# vswr_power_eagle.net
KiCad netlist of a schematic drawn in EAGLE
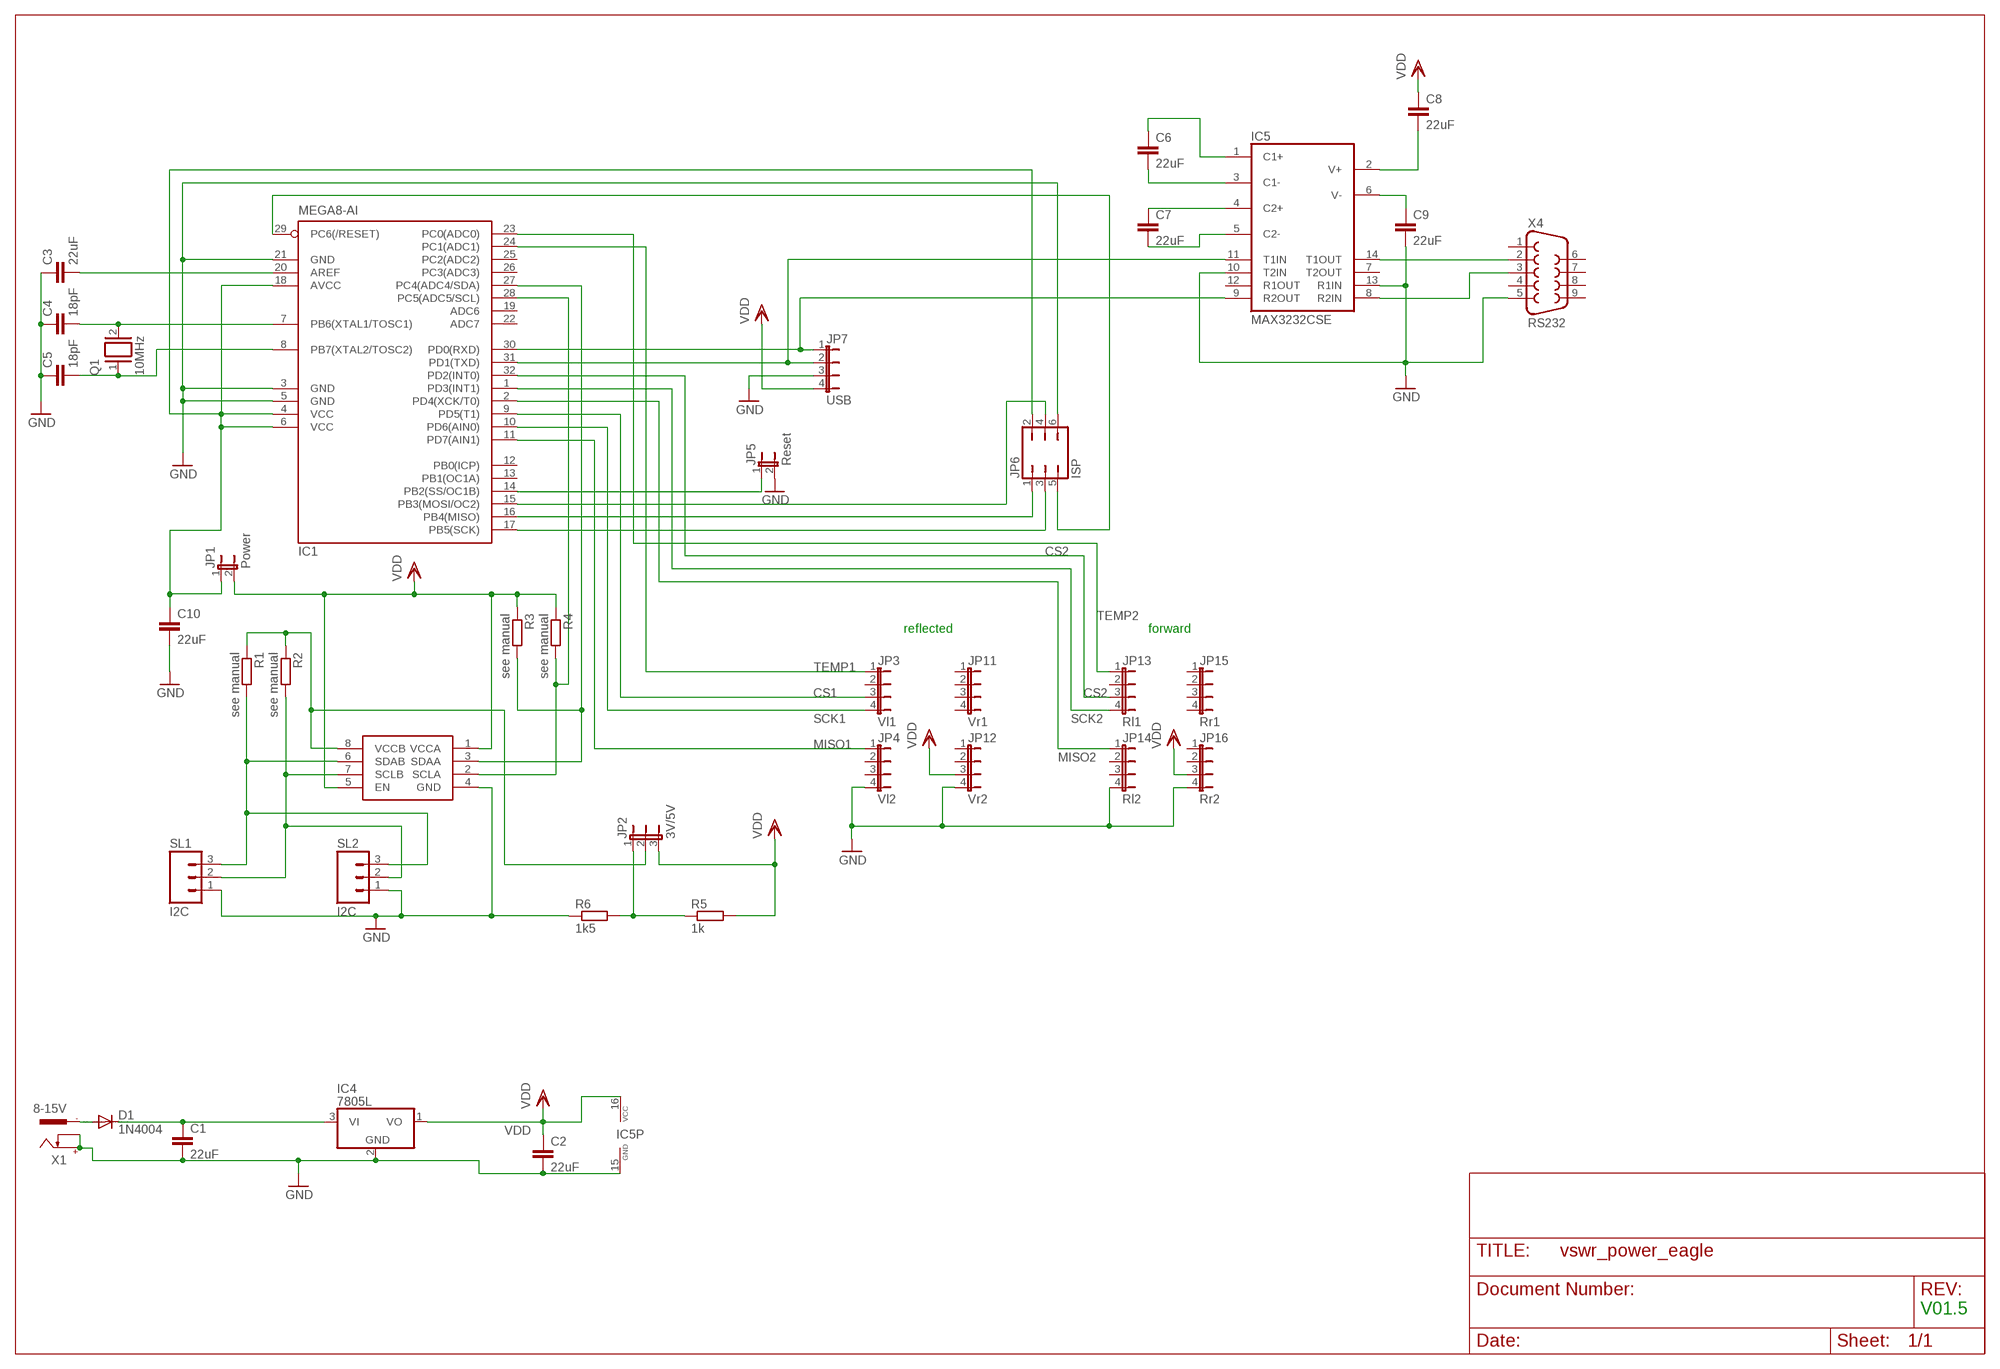
[diagram p0: schematic, sheet 1]

(export (version "E")
  (design (tool "Eeschema 10.0.6"))
  (components
    (comp (ref "C1")
      (value "22uF")
      (footprint "eagle-import:C1206")
      (libsource (lib "eagle-import") (part "C-EUC1206"))
    )
    (comp (ref "C2")
      (value "22uF")
      (footprint "eagle-import:C1206")
      (libsource (lib "eagle-import") (part "C-EUC1206"))
    )
    (comp (ref "C3")
      (value "22uF")
      (footprint "eagle-import:C1206")
      (libsource (lib "eagle-import") (part "C-EUC1206"))
    )
    (comp (ref "C4")
      (value "18pF")
      (footprint "eagle-import:C025-025X050")
      (libsource (lib "eagle-import") (part "resistor_C-EU025-025X050"))
    )
    (comp (ref "C5")
      (value "18pF")
      (footprint "eagle-import:C025-025X050")
      (libsource (lib "eagle-import") (part "resistor_C-EU025-025X050"))
    )
    (comp (ref "C6")
      (value "22uF")
      (footprint "eagle-import:C1206")
      (libsource (lib "eagle-import") (part "C-EUC1206"))
    )
    (comp (ref "C7")
      (value "22uF")
      (footprint "eagle-import:C1206")
      (libsource (lib "eagle-import") (part "C-EUC1206"))
    )
    (comp (ref "C8")
      (value "22uF")
      (footprint "eagle-import:C1206")
      (libsource (lib "eagle-import") (part "C-EUC1206"))
    )
    (comp (ref "C9")
      (value "22uF")
      (footprint "eagle-import:C1206")
      (libsource (lib "eagle-import") (part "C-EUC1206"))
    )
    (comp (ref "C10")
      (value "22uF")
      (footprint "eagle-import:C1206")
      (libsource (lib "eagle-import") (part "C-EUC1206"))
    )
    (comp (ref "D1")
      (value "1N4004")
      (footprint "eagle-import:DO41-10")
      (libsource (lib "eagle-import") (part "1N4004"))
    )
    (comp (ref "IC1")
      (value "MEGA8-AI")
      (footprint "eagle-import:TQFP32-08")
      (fields (field (name "MPN") "ATMEGA8-16AU"))
      (libsource (lib "eagle-import") (part "MEGA8-AI"))
    )
    (comp (ref "IC3")
      (value "PCA9517")
      (footprint "eagle-import:SO-08")
      (libsource (lib "eagle-import") (part "PCA9517"))
    )
    (comp (ref "IC4")
      (value "7805L")
      (footprint "eagle-import:TO92")
      (libsource (lib "eagle-import") (part "78L05"))
    )
    (comp (ref "IC5")
      (value "MAX3232CSE")
      (footprint "eagle-import:SO16")
      (libsource (lib "eagle-import") (part "MAX3232SEC"))
    )
    (comp (ref "JP1")
      (value "Power")
      (footprint "eagle-import:JP1")
      (libsource (lib "eagle-import") (part "JP1E"))
    )
    (comp (ref "JP2")
      (value "3V/5V")
      (footprint "eagle-import:JP2")
      (libsource (lib "eagle-import") (part "JP2E"))
    )
    (comp (ref "JP3")
      (value "Vl1")
      (footprint "eagle-import:JP4")
      (libsource (lib "eagle-import") (part "JP4E"))
    )
    (comp (ref "JP4")
      (value "Vl2")
      (footprint "eagle-import:JP4")
      (libsource (lib "eagle-import") (part "JP4E"))
    )
    (comp (ref "JP5")
      (value "Reset")
      (footprint "eagle-import:JP1")
      (libsource (lib "eagle-import") (part "JP1E"))
    )
    (comp (ref "JP6")
      (value "ISP")
      (footprint "eagle-import:JP3Q")
      (libsource (lib "eagle-import") (part "JP3Q"))
    )
    (comp (ref "JP7")
      (value "USB")
      (footprint "eagle-import:JP4")
      (libsource (lib "eagle-import") (part "JP4E"))
    )
    (comp (ref "JP11")
      (value "Vr1")
      (footprint "eagle-import:JP4")
      (libsource (lib "eagle-import") (part "JP4E"))
    )
    (comp (ref "JP12")
      (value "Vr2")
      (footprint "eagle-import:JP4")
      (libsource (lib "eagle-import") (part "JP4E"))
    )
    (comp (ref "JP13")
      (value "Rl1")
      (footprint "eagle-import:JP4")
      (libsource (lib "eagle-import") (part "JP4E"))
    )
    (comp (ref "JP14")
      (value "Rl2")
      (footprint "eagle-import:JP4")
      (libsource (lib "eagle-import") (part "JP4E"))
    )
    (comp (ref "JP15")
      (value "Rr1")
      (footprint "eagle-import:JP4")
      (libsource (lib "eagle-import") (part "JP4E"))
    )
    (comp (ref "JP16")
      (value "Rr2")
      (footprint "eagle-import:JP4")
      (libsource (lib "eagle-import") (part "JP4E"))
    )
    (comp (ref "Q1")
      (value "10MHz")
      (footprint "eagle-import:QS")
      (libsource (lib "eagle-import") (part "XTAL/S"))
    )
    (comp (ref "R1")
      (value "see manual")
      (footprint "eagle-import:R1206")
      (libsource (lib "eagle-import") (part "R-EU_R1206"))
    )
    (comp (ref "R2")
      (value "see manual")
      (footprint "eagle-import:R1206")
      (libsource (lib "eagle-import") (part "R-EU_R1206"))
    )
    (comp (ref "R3")
      (value "see manual")
      (footprint "eagle-import:R1206")
      (libsource (lib "eagle-import") (part "R-EU_R1206"))
    )
    (comp (ref "R4")
      (value "see manual")
      (footprint "eagle-import:R1206")
      (libsource (lib "eagle-import") (part "R-EU_R1206"))
    )
    (comp (ref "R5")
      (value "1k")
      (footprint "eagle-import:R1206")
      (libsource (lib "eagle-import") (part "R-EU_R1206"))
    )
    (comp (ref "R6")
      (value "1k5")
      (footprint "eagle-import:R1206")
      (libsource (lib "eagle-import") (part "R-EU_R1206"))
    )
    (comp (ref "SL1")
      (value "I2C")
      (footprint "eagle-import:03P")
      (libsource (lib "eagle-import") (part "M03"))
    )
    (comp (ref "SL2")
      (value "I2C")
      (footprint "eagle-import:03P")
      (libsource (lib "eagle-import") (part "M03"))
    )
    (comp (ref "X1")
      (value "8-15V")
      (footprint "eagle-import:737992-5")
      (libsource (lib "eagle-import") (part "737992-55"))
    )
    (comp (ref "X4")
      (value "RS232")
      (footprint "eagle-import:F09H")
      (libsource (lib "eagle-import") (part "F09H"))
    )
  )
  (nets
    (net (code "1") (name "/CS1") (class "Default")
      (node (ref "IC1") (pin "9") (pinfunction "PD5(T1)_9") (pintype "bidirectional"))
      (node (ref "JP3") (pin "3") (pinfunction "3_3") (pintype "passive"))
    )
    (net (code "2") (name "/CS2") (class "Default")
      (node (ref "IC1") (pin "32") (pinfunction "PD2(INT0)_32") (pintype "bidirectional"))
      (node (ref "JP13") (pin "3") (pinfunction "3_3") (pintype "passive"))
    )
    (net (code "3") (name "/MISO1") (class "Default")
      (node (ref "IC1") (pin "11") (pinfunction "PD7(AIN1)_11") (pintype "bidirectional"))
      (node (ref "JP4") (pin "1") (pinfunction "1_1") (pintype "passive"))
    )
    (net (code "4") (name "/MISO2") (class "Default")
      (node (ref "IC1") (pin "2") (pinfunction "PD4(XCK/T0)_2") (pintype "bidirectional"))
      (node (ref "JP14") (pin "1") (pinfunction "1_1") (pintype "passive"))
    )
    (net (code "5") (name "/SCK1") (class "Default")
      (node (ref "IC1") (pin "10") (pinfunction "PD6(AIN0)_10") (pintype "bidirectional"))
      (node (ref "JP3") (pin "4") (pinfunction "4_4") (pintype "passive"))
    )
    (net (code "6") (name "/SCK2") (class "Default")
      (node (ref "IC1") (pin "1") (pinfunction "PD3(INT1)_1") (pintype "bidirectional"))
      (node (ref "JP13") (pin "4") (pinfunction "4_4") (pintype "passive"))
    )
    (net (code "7") (name "/TEMP1") (class "Default")
      (node (ref "IC1") (pin "24") (pinfunction "PC1(ADC1)_24") (pintype "bidirectional"))
      (node (ref "JP3") (pin "1") (pinfunction "1_1") (pintype "passive"))
    )
    (net (code "8") (name "/TEMP2") (class "Default")
      (node (ref "IC1") (pin "23") (pinfunction "PC0(ADC0)_23") (pintype "bidirectional"))
      (node (ref "JP13") (pin "1") (pinfunction "1_1") (pintype "passive"))
    )
    (net (code "9") (name "GND") (class "Default")
      (node (ref "C1") (pin "2") (pinfunction "2_2") (pintype "passive"))
      (node (ref "C10") (pin "2") (pinfunction "2_2") (pintype "passive"))
      (node (ref "C2") (pin "2") (pinfunction "2_2") (pintype "passive"))
      (node (ref "C3") (pin "1") (pinfunction "1_1") (pintype "passive"))
      (node (ref "C4") (pin "1") (pinfunction "1_1") (pintype "passive"))
      (node (ref "C5") (pin "1") (pinfunction "1_1") (pintype "passive"))
      (node (ref "C9") (pin "2") (pinfunction "2_2") (pintype "passive"))
      (node (ref "IC1") (pin "21") (pinfunction "GND_21") (pintype "power_in"))
      (node (ref "IC1") (pin "3") (pinfunction "GND_3") (pintype "power_in"))
      (node (ref "IC1") (pin "5") (pinfunction "GND_5") (pintype "power_in"))
      (node (ref "IC3") (pin "4") (pinfunction "GND_4") (pintype "bidirectional"))
      (node (ref "IC4") (pin "2") (pinfunction "GND_2") (pintype "passive"))
      (node (ref "IC5") (pin "10") (pinfunction "T2IN_10") (pintype "input"))
      (node (ref "IC5") (pin "13") (pinfunction "R1IN_13") (pintype "input"))
      (node (ref "IC5") (pin "15") (pinfunction "GND_15") (pintype "power_in"))
      (node (ref "JP12") (pin "4") (pinfunction "4_4") (pintype "passive"))
      (node (ref "JP14") (pin "4") (pinfunction "4_4") (pintype "passive"))
      (node (ref "JP16") (pin "4") (pinfunction "4_4") (pintype "passive"))
      (node (ref "JP4") (pin "4") (pinfunction "4_4") (pintype "passive"))
      (node (ref "JP5") (pin "2") (pinfunction "2_2") (pintype "passive"))
      (node (ref "JP6") (pin "6") (pinfunction "6_6") (pintype "passive"))
      (node (ref "JP7") (pin "3") (pinfunction "3_3") (pintype "passive"))
      (node (ref "R6") (pin "1") (pinfunction "1_1") (pintype "passive"))
      (node (ref "SL1") (pin "1") (pinfunction "1_1") (pintype "passive"))
      (node (ref "SL2") (pin "1") (pinfunction "1_1") (pintype "passive"))
      (node (ref "X1") (pin "+") (pinfunction "+_+") (pintype "passive"))
      (node (ref "X1") (pin "K") (pinfunction "K_K") (pintype "passive"))
      (node (ref "X4") (pin "5") (pinfunction "5_5") (pintype "passive"))
    )
    (net (code "10") (name "Net-(D1-PadA)") (class "Default")
      (node (ref "D1") (pin "A") (pinfunction "A_A") (pintype "passive"))
      (node (ref "X1") (pin "-1") (pinfunction "-1_-1") (pintype "passive"))
    )
    (net (code "11") (name "Net-(IC1-AREF)") (class "Default")
      (node (ref "C3") (pin "2") (pinfunction "2_2") (pintype "passive"))
      (node (ref "IC1") (pin "20") (pinfunction "AREF_20") (pintype "passive"))
    )
    (net (code "12") (name "Net-(IC1-AVCC)") (class "Default")
      (node (ref "C10") (pin "1") (pinfunction "1_1") (pintype "passive"))
      (node (ref "IC1") (pin "18") (pinfunction "AVCC_18") (pintype "power_in"))
      (node (ref "IC1") (pin "4") (pinfunction "VCC_4") (pintype "power_in"))
      (node (ref "IC1") (pin "6") (pinfunction "VCC_6") (pintype "power_in"))
      (node (ref "JP1") (pin "1") (pinfunction "1_1") (pintype "passive"))
      (node (ref "JP6") (pin "2") (pinfunction "2_2") (pintype "passive"))
    )
    (net (code "13") (name "Net-(IC1-PB2(SS{slash}OC1B))") (class "Default")
      (node (ref "IC1") (pin "14") (pinfunction "PB2(SS/OC1B)_14") (pintype "bidirectional"))
      (node (ref "JP5") (pin "1") (pinfunction "1_1") (pintype "passive"))
    )
    (net (code "14") (name "Net-(IC1-PB3(MOSI{slash}OC2))") (class "Default")
      (node (ref "IC1") (pin "15") (pinfunction "PB3(MOSI/OC2)_15") (pintype "bidirectional"))
      (node (ref "JP6") (pin "4") (pinfunction "4_4") (pintype "passive"))
    )
    (net (code "15") (name "Net-(IC1-PB4(MISO))") (class "Default")
      (node (ref "IC1") (pin "16") (pinfunction "PB4(MISO)_16") (pintype "bidirectional"))
      (node (ref "JP6") (pin "1") (pinfunction "1_1") (pintype "passive"))
    )
    (net (code "16") (name "Net-(IC1-PB5(SCK))") (class "Default")
      (node (ref "IC1") (pin "17") (pinfunction "PB5(SCK)_17") (pintype "bidirectional"))
      (node (ref "JP6") (pin "3") (pinfunction "3_3") (pintype "passive"))
    )
    (net (code "17") (name "Net-(IC1-PB6(XTAL1{slash}TOSC1))") (class "Default")
      (node (ref "C4") (pin "2") (pinfunction "2_2") (pintype "passive"))
      (node (ref "IC1") (pin "7") (pinfunction "PB6(XTAL1/TOSC1)_7") (pintype "bidirectional"))
      (node (ref "Q1") (pin "2") (pinfunction "2_2") (pintype "passive"))
    )
    (net (code "18") (name "Net-(IC1-PB7(XTAL2{slash}TOSC2))") (class "Default")
      (node (ref "C5") (pin "2") (pinfunction "2_2") (pintype "passive"))
      (node (ref "IC1") (pin "8") (pinfunction "PB7(XTAL2/TOSC2)_8") (pintype "bidirectional"))
      (node (ref "Q1") (pin "1") (pinfunction "1_1") (pintype "passive"))
    )
    (net (code "19") (name "Net-(IC1-PC4(ADC4{slash}SDA))") (class "Default")
      (node (ref "IC1") (pin "27") (pinfunction "PC4(ADC4/SDA)_27") (pintype "bidirectional"))
      (node (ref "IC3") (pin "3") (pinfunction "SDAA_3") (pintype "bidirectional"))
      (node (ref "R3") (pin "2") (pinfunction "2_2") (pintype "passive"))
    )
    (net (code "20") (name "Net-(IC1-PC5(ADC5{slash}SCL))") (class "Default")
      (node (ref "IC1") (pin "28") (pinfunction "PC5(ADC5/SCL)_28") (pintype "bidirectional"))
      (node (ref "IC3") (pin "2") (pinfunction "SCLA_2") (pintype "bidirectional"))
      (node (ref "R4") (pin "2") (pinfunction "2_2") (pintype "passive"))
    )
    (net (code "21") (name "Net-(IC1-PC6({slash}RESET))") (class "Default")
      (node (ref "IC1") (pin "29") (pinfunction "PC6(/RESET)_29") (pintype "bidirectional"))
      (node (ref "JP6") (pin "5") (pinfunction "5_5") (pintype "passive"))
    )
    (net (code "22") (name "Net-(IC1-PD0(RXD))") (class "Default")
      (node (ref "IC1") (pin "30") (pinfunction "PD0(RXD)_30") (pintype "bidirectional"))
      (node (ref "IC5") (pin "9") (pinfunction "R2OUT_9") (pintype "output"))
      (node (ref "JP7") (pin "1") (pinfunction "1_1") (pintype "passive"))
    )
    (net (code "23") (name "Net-(IC1-PD1(TXD))") (class "Default")
      (node (ref "IC1") (pin "31") (pinfunction "PD1(TXD)_31") (pintype "bidirectional"))
      (node (ref "IC5") (pin "11") (pinfunction "T1IN_11") (pintype "input"))
      (node (ref "JP7") (pin "2") (pinfunction "2_2") (pintype "passive"))
    )
    (net (code "24") (name "Net-(IC3-SCLB)") (class "Default")
      (node (ref "IC3") (pin "7") (pinfunction "SCLB_7") (pintype "bidirectional"))
      (node (ref "R2") (pin "2") (pinfunction "2_2") (pintype "passive"))
      (node (ref "SL1") (pin "2") (pinfunction "2_2") (pintype "passive"))
      (node (ref "SL2") (pin "2") (pinfunction "2_2") (pintype "passive"))
    )
    (net (code "25") (name "Net-(IC3-SDAB)") (class "Default")
      (node (ref "IC3") (pin "6") (pinfunction "SDAB_6") (pintype "bidirectional"))
      (node (ref "R1") (pin "2") (pinfunction "2_2") (pintype "passive"))
      (node (ref "SL1") (pin "3") (pinfunction "3_3") (pintype "passive"))
      (node (ref "SL2") (pin "3") (pinfunction "3_3") (pintype "passive"))
    )
    (net (code "26") (name "Net-(IC3-VCCB)") (class "Default")
      (node (ref "IC3") (pin "8") (pinfunction "VCCB_8") (pintype "bidirectional"))
      (node (ref "JP2") (pin "2") (pinfunction "2_2") (pintype "passive"))
      (node (ref "R1") (pin "1") (pinfunction "1_1") (pintype "passive"))
      (node (ref "R2") (pin "1") (pinfunction "1_1") (pintype "passive"))
    )
    (net (code "27") (name "Net-(IC4-VI)") (class "Default")
      (node (ref "C1") (pin "1") (pinfunction "1_1") (pintype "passive"))
      (node (ref "D1") (pin "C") (pinfunction "C_C") (pintype "passive"))
      (node (ref "IC4") (pin "3") (pinfunction "VI_3") (pintype "input"))
    )
    (net (code "28") (name "Net-(IC5A-C1+)") (class "Default")
      (node (ref "C6") (pin "1") (pinfunction "1_1") (pintype "passive"))
      (node (ref "IC5") (pin "1") (pinfunction "C1+_1") (pintype "bidirectional"))
    )
    (net (code "29") (name "Net-(IC5A-C1-)") (class "Default")
      (node (ref "C6") (pin "2") (pinfunction "2_2") (pintype "passive"))
      (node (ref "IC5") (pin "3") (pinfunction "C1-_3") (pintype "bidirectional"))
    )
    (net (code "30") (name "Net-(IC5A-C2+)") (class "Default")
      (node (ref "C7") (pin "1") (pinfunction "1_1") (pintype "passive"))
      (node (ref "IC5") (pin "4") (pinfunction "C2+_4") (pintype "bidirectional"))
    )
    (net (code "31") (name "Net-(IC5A-C2-)") (class "Default")
      (node (ref "C7") (pin "2") (pinfunction "2_2") (pintype "passive"))
      (node (ref "IC5") (pin "5") (pinfunction "C2-_5") (pintype "bidirectional"))
    )
    (net (code "32") (name "Net-(IC5A-R2IN)") (class "Default")
      (node (ref "IC5") (pin "8") (pinfunction "R2IN_8") (pintype "input"))
      (node (ref "X4") (pin "3") (pinfunction "3_3") (pintype "passive"))
    )
    (net (code "33") (name "Net-(IC5A-T1OUT)") (class "Default")
      (node (ref "IC5") (pin "14") (pinfunction "T1OUT_14") (pintype "output"))
      (node (ref "X4") (pin "2") (pinfunction "2_2") (pintype "passive"))
    )
    (net (code "34") (name "Net-(IC5A-V+)") (class "Default")
      (node (ref "C8") (pin "2") (pinfunction "2_2") (pintype "passive"))
      (node (ref "IC5") (pin "2") (pinfunction "V+_2") (pintype "bidirectional"))
    )
    (net (code "35") (name "Net-(IC5A-V-)") (class "Default")
      (node (ref "C9") (pin "1") (pinfunction "1_1") (pintype "passive"))
      (node (ref "IC5") (pin "6") (pinfunction "V-_6") (pintype "bidirectional"))
    )
    (net (code "36") (name "Net-(JP2-Pad1)") (class "Default")
      (node (ref "JP2") (pin "1") (pinfunction "1_1") (pintype "passive"))
      (node (ref "R5") (pin "1") (pinfunction "1_1") (pintype "passive"))
      (node (ref "R6") (pin "2") (pinfunction "2_2") (pintype "passive"))
    )
    (net (code "37") (name "VDD") (class "Default")
      (node (ref "C2") (pin "1") (pinfunction "1_1") (pintype "passive"))
      (node (ref "C8") (pin "1") (pinfunction "1_1") (pintype "passive"))
      (node (ref "IC3") (pin "1") (pinfunction "VCCA_1") (pintype "bidirectional"))
      (node (ref "IC3") (pin "5") (pinfunction "EN_5") (pintype "bidirectional"))
      (node (ref "IC4") (pin "1") (pinfunction "VO_1") (pintype "passive"))
      (node (ref "IC5") (pin "16") (pinfunction "VCC_16") (pintype "power_in"))
      (node (ref "JP1") (pin "2") (pinfunction "2_2") (pintype "passive"))
      (node (ref "JP12") (pin "3") (pinfunction "3_3") (pintype "passive"))
      (node (ref "JP16") (pin "3") (pinfunction "3_3") (pintype "passive"))
      (node (ref "JP2") (pin "3") (pinfunction "3_3") (pintype "passive"))
      (node (ref "JP7") (pin "4") (pinfunction "4_4") (pintype "passive"))
      (node (ref "R3") (pin "1") (pinfunction "1_1") (pintype "passive"))
      (node (ref "R4") (pin "1") (pinfunction "1_1") (pintype "passive"))
      (node (ref "R5") (pin "2") (pinfunction "2_2") (pintype "passive"))
    )
    (net (code "38") (name "unconnected-(IC1-ADC6-Pad19)") (class "Default")
      (node (ref "IC1") (pin "19") (pinfunction "ADC6_19") (pintype "bidirectional"))
    )
    (net (code "39") (name "unconnected-(IC1-ADC7-Pad22)") (class "Default")
      (node (ref "IC1") (pin "22") (pinfunction "ADC7_22") (pintype "bidirectional"))
    )
    (net (code "40") (name "unconnected-(IC1-PB0(ICP)-Pad12)") (class "Default")
      (node (ref "IC1") (pin "12") (pinfunction "PB0(ICP)_12") (pintype "bidirectional"))
    )
    (net (code "41") (name "unconnected-(IC1-PB1(OC1A)-Pad13)") (class "Default")
      (node (ref "IC1") (pin "13") (pinfunction "PB1(OC1A)_13") (pintype "bidirectional"))
    )
    (net (code "42") (name "unconnected-(IC1-PC2(ADC2)-Pad25)") (class "Default")
      (node (ref "IC1") (pin "25") (pinfunction "PC2(ADC2)_25") (pintype "bidirectional"))
    )
    (net (code "43") (name "unconnected-(IC1-PC3(ADC3)-Pad26)") (class "Default")
      (node (ref "IC1") (pin "26") (pinfunction "PC3(ADC3)_26") (pintype "bidirectional"))
    )
    (net (code "44") (name "unconnected-(IC5A-R1OUT-Pad12)") (class "Default")
      (node (ref "IC5") (pin "12") (pinfunction "R1OUT_12") (pintype "output"))
    )
    (net (code "45") (name "unconnected-(IC5A-T2OUT-Pad7)") (class "Default")
      (node (ref "IC5") (pin "7") (pinfunction "T2OUT_7") (pintype "output"))
    )
    (net (code "46") (name "unconnected-(JP3-Pad2)") (class "Default")
      (node (ref "JP3") (pin "2") (pinfunction "2_2") (pintype "passive"))
    )
    (net (code "47") (name "unconnected-(JP4-Pad2)") (class "Default")
      (node (ref "JP4") (pin "2") (pinfunction "2_2") (pintype "passive"))
    )
    (net (code "48") (name "unconnected-(JP4-Pad3)") (class "Default")
      (node (ref "JP4") (pin "3") (pinfunction "3_3") (pintype "passive"))
    )
    (net (code "49") (name "unconnected-(JP11-Pad1)") (class "Default")
      (node (ref "JP11") (pin "1") (pinfunction "1_1") (pintype "passive"))
    )
    (net (code "50") (name "unconnected-(JP11-Pad2)") (class "Default")
      (node (ref "JP11") (pin "2") (pinfunction "2_2") (pintype "passive"))
    )
    (net (code "51") (name "unconnected-(JP11-Pad3)") (class "Default")
      (node (ref "JP11") (pin "3") (pinfunction "3_3") (pintype "passive"))
    )
    (net (code "52") (name "unconnected-(JP11-Pad4)") (class "Default")
      (node (ref "JP11") (pin "4") (pinfunction "4_4") (pintype "passive"))
    )
    (net (code "53") (name "unconnected-(JP12-Pad1)") (class "Default")
      (node (ref "JP12") (pin "1") (pinfunction "1_1") (pintype "passive"))
    )
    (net (code "54") (name "unconnected-(JP12-Pad2)") (class "Default")
      (node (ref "JP12") (pin "2") (pinfunction "2_2") (pintype "passive"))
    )
    (net (code "55") (name "unconnected-(JP13-Pad2)") (class "Default")
      (node (ref "JP13") (pin "2") (pinfunction "2_2") (pintype "passive"))
    )
    (net (code "56") (name "unconnected-(JP14-Pad2)") (class "Default")
      (node (ref "JP14") (pin "2") (pinfunction "2_2") (pintype "passive"))
    )
    (net (code "57") (name "unconnected-(JP14-Pad3)") (class "Default")
      (node (ref "JP14") (pin "3") (pinfunction "3_3") (pintype "passive"))
    )
    (net (code "58") (name "unconnected-(JP15-Pad1)") (class "Default")
      (node (ref "JP15") (pin "1") (pinfunction "1_1") (pintype "passive"))
    )
    (net (code "59") (name "unconnected-(JP15-Pad2)") (class "Default")
      (node (ref "JP15") (pin "2") (pinfunction "2_2") (pintype "passive"))
    )
    (net (code "60") (name "unconnected-(JP15-Pad3)") (class "Default")
      (node (ref "JP15") (pin "3") (pinfunction "3_3") (pintype "passive"))
    )
    (net (code "61") (name "unconnected-(JP15-Pad4)") (class "Default")
      (node (ref "JP15") (pin "4") (pinfunction "4_4") (pintype "passive"))
    )
    (net (code "62") (name "unconnected-(JP16-Pad1)") (class "Default")
      (node (ref "JP16") (pin "1") (pinfunction "1_1") (pintype "passive"))
    )
    (net (code "63") (name "unconnected-(JP16-Pad2)") (class "Default")
      (node (ref "JP16") (pin "2") (pinfunction "2_2") (pintype "passive"))
    )
    (net (code "64") (name "unconnected-(X1-Pad-2)") (class "Default")
      (node (ref "X1") (pin "-2") (pinfunction "-2_-2") (pintype "passive"))
    )
    (net (code "65") (name "unconnected-(X4-Pad1)") (class "Default")
      (node (ref "X4") (pin "1") (pinfunction "1_1") (pintype "passive"))
    )
    (net (code "66") (name "unconnected-(X4-Pad4)") (class "Default")
      (node (ref "X4") (pin "4") (pinfunction "4_4") (pintype "passive"))
    )
    (net (code "67") (name "unconnected-(X4-Pad6)") (class "Default")
      (node (ref "X4") (pin "6") (pinfunction "6_6") (pintype "passive"))
    )
    (net (code "68") (name "unconnected-(X4-Pad7)") (class "Default")
      (node (ref "X4") (pin "7") (pinfunction "7_7") (pintype "passive"))
    )
    (net (code "69") (name "unconnected-(X4-Pad8)") (class "Default")
      (node (ref "X4") (pin "8") (pinfunction "8_8") (pintype "passive"))
    )
    (net (code "70") (name "unconnected-(X4-Pad9)") (class "Default")
      (node (ref "X4") (pin "9") (pinfunction "9_9") (pintype "passive"))
    )
  )
)
